# Constant_Current_LED_Driver_v01.net
KiCad netlist of a schematic drawn in EAGLE
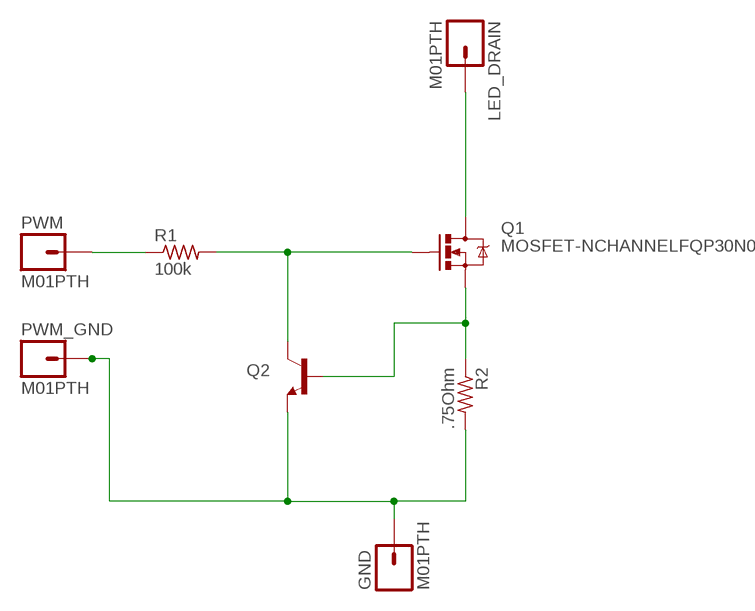
[diagram p0: schematic, sheet 1]

(export (version "E")
  (design (tool "Eeschema 10.0.6"))
  (components
    (comp (ref "GND")
      (value "M01PTH")
      (footprint "eagle-import:1X01")
      (libsource (lib "eagle-import") (part "M01PTH"))
    )
    (comp (ref "LED_DRAIN")
      (value "M01PTH")
      (footprint "eagle-import:1X01")
      (libsource (lib "eagle-import") (part "M01PTH"))
    )
    (comp (ref "PWM")
      (value "M01PTH")
      (footprint "eagle-import:1X01")
      (libsource (lib "eagle-import") (part "M01PTH"))
    )
    (comp (ref "PWM_GND")
      (value "M01PTH")
      (footprint "eagle-import:1X01")
      (libsource (lib "eagle-import") (part "M01PTH"))
    )
    (comp (ref "Q1")
      (value "MOSFET-NCHANNELFQP30N06L")
      (footprint "eagle-import:TO220V")
      (libsource (lib "eagle-import") (part "MOSFET-NCHANNELFQP30N06L"))
    )
    (comp (ref "Q2")
      (value "TRANSISTOR_NPNTO92")
      (footprint "eagle-import:TO-92")
      (libsource (lib "eagle-import") (part "TRANSISTOR_NPNTO92"))
    )
    (comp (ref "R1")
      (value "100k")
      (footprint "eagle-import:R0805W")
      (libsource (lib "eagle-import") (part "R-US_R0805W"))
    )
    (comp (ref "R2")
      (value ".75Ohm")
      (footprint "eagle-import:0204_5")
      (libsource (lib "eagle-import") (part "R-US_0204/5"))
    )
  )
  (nets
    (net (code "1") (name "Net-(PWM-Pad1)") (class "Default")
      (node (ref "PWM") (pin "1") (pinfunction "1_1") (pintype "passive"))
      (node (ref "R1") (pin "1") (pinfunction "1_1") (pintype "passive"))
    )
    (net (code "2") (name "Net-(Q1-D)") (class "Default")
      (node (ref "LED_DRAIN") (pin "1") (pinfunction "1_1") (pintype "passive"))
      (node (ref "Q1") (pin "2") (pinfunction "D_2") (pintype "passive"))
    )
    (net (code "3") (name "Net-(Q1-G)") (class "Default")
      (node (ref "Q1") (pin "1") (pinfunction "G_1") (pintype "passive"))
      (node (ref "Q2") (pin "3") (pinfunction "C_3") (pintype "passive"))
      (node (ref "R1") (pin "2") (pinfunction "2_2") (pintype "passive"))
    )
    (net (code "4") (name "Net-(Q1-S)") (class "Default")
      (node (ref "Q1") (pin "3") (pinfunction "S_3") (pintype "passive"))
      (node (ref "Q2") (pin "2") (pinfunction "B_2") (pintype "passive"))
      (node (ref "R2") (pin "1") (pinfunction "1_1") (pintype "passive"))
    )
    (net (code "5") (name "Net-(Q2-E)") (class "Default")
      (node (ref "GND") (pin "1") (pinfunction "1_1") (pintype "passive"))
      (node (ref "PWM_GND") (pin "1") (pinfunction "1_1") (pintype "passive"))
      (node (ref "Q2") (pin "1") (pinfunction "E_1") (pintype "passive"))
      (node (ref "R2") (pin "2") (pinfunction "2_2") (pintype "passive"))
    )
  )
)
